# Router.net
KiCad netlist of a schematic drawn in EAGLE
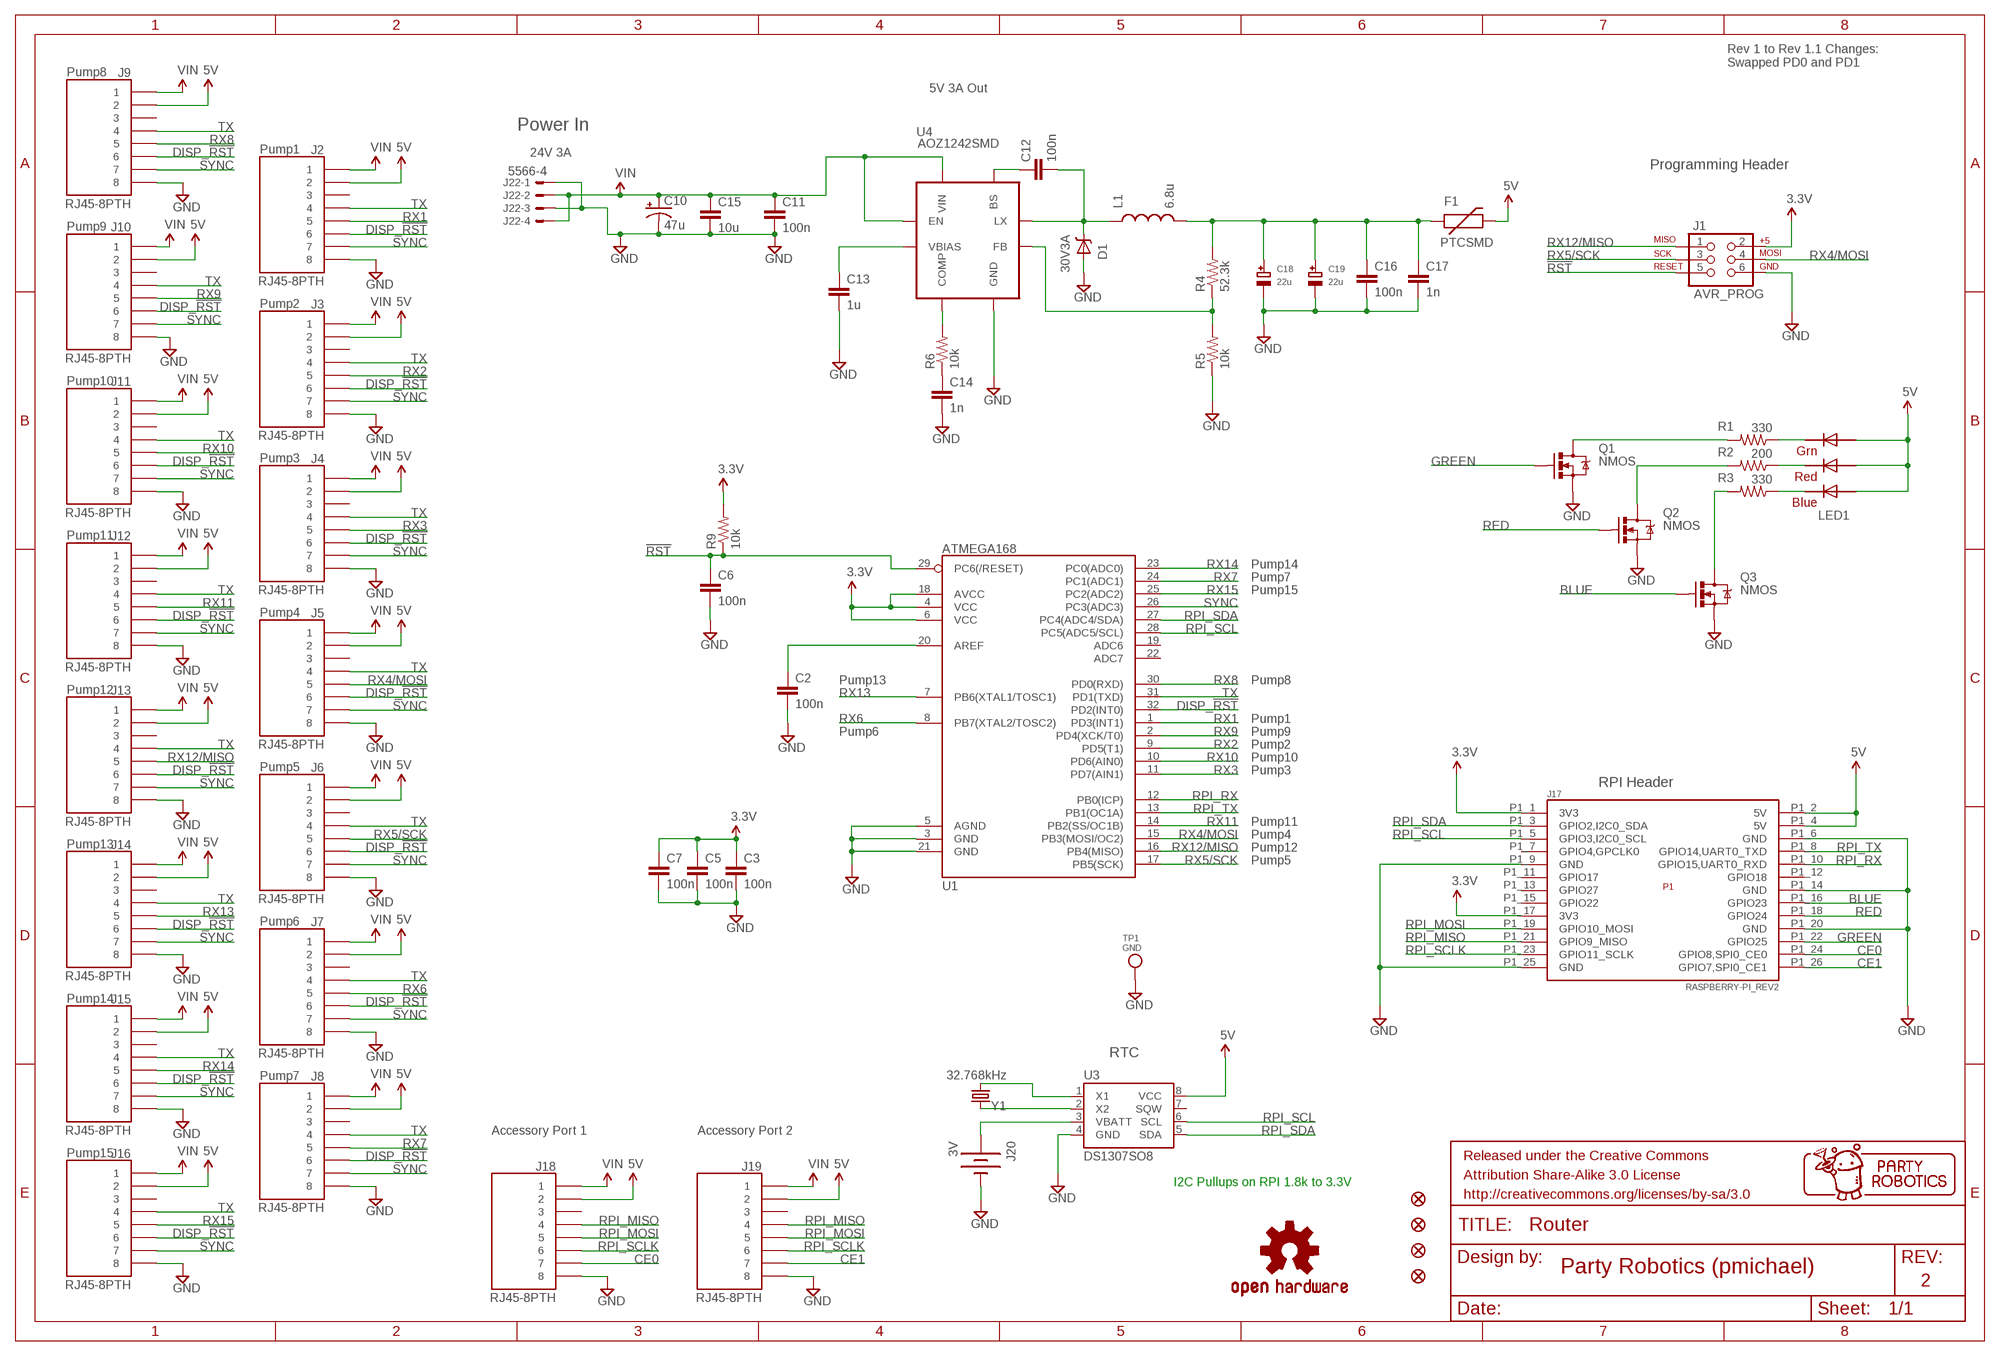
[diagram p0: schematic, sheet 1]

(export (version "E")
  (design (tool "Eeschema 10.0.6"))
  (components
    (comp (ref "C2")
      (value "100n")
      (footprint "eagle-import:0603-CAP")
      (libsource (lib "eagle-import") (part "CAP0603-CAP"))
    )
    (comp (ref "C3")
      (value "100n")
      (footprint "eagle-import:0603-CAP")
      (libsource (lib "eagle-import") (part "CAP0603-CAP"))
    )
    (comp (ref "C5")
      (value "100n")
      (footprint "eagle-import:0603-CAP")
      (libsource (lib "eagle-import") (part "CAP0603-CAP"))
    )
    (comp (ref "C6")
      (value "100n")
      (footprint "eagle-import:0603-CAP")
      (libsource (lib "eagle-import") (part "CAP0603-CAP"))
    )
    (comp (ref "C7")
      (value "100n")
      (footprint "eagle-import:0603-CAP")
      (libsource (lib "eagle-import") (part "CAP0603-CAP"))
    )
    (comp (ref "C10")
      (value "47u")
      (footprint "eagle-import:PANASONIC_D")
      (libsource (lib "eagle-import") (part "CAP_POLD"))
    )
    (comp (ref "C11")
      (value "100n")
      (footprint "eagle-import:0603-CAP")
      (libsource (lib "eagle-import") (part "CAP0603-CAP"))
    )
    (comp (ref "C12")
      (value "100n")
      (footprint "eagle-import:0603-CAP")
      (libsource (lib "eagle-import") (part "CAP0603-CAP"))
    )
    (comp (ref "C13")
      (value "1u")
      (footprint "eagle-import:0603-CAP")
      (libsource (lib "eagle-import") (part "CAP0603-CAP"))
    )
    (comp (ref "C14")
      (value "1n")
      (footprint "eagle-import:0603-CAP")
      (libsource (lib "eagle-import") (part "CAP0603-CAP"))
    )
    (comp (ref "C15")
      (value "10u")
      (footprint "eagle-import:1206")
      (libsource (lib "eagle-import") (part "SparkFun-Capacitors_CAP1206"))
    )
    (comp (ref "C16")
      (value "100n")
      (footprint "eagle-import:0603-CAP")
      (libsource (lib "eagle-import") (part "CAP0603-CAP"))
    )
    (comp (ref "C17")
      (value "1n")
      (footprint "eagle-import:0603-CAP")
      (libsource (lib "eagle-import") (part "CAP0603-CAP"))
    )
    (comp (ref "C18")
      (value "22u")
      (footprint "eagle-import:EIA6032-28_C-R")
      (libsource (lib "eagle-import") (part "CAP_TANTALUMC/6032_REFLOW"))
    )
    (comp (ref "C19")
      (value "22u")
      (footprint "eagle-import:EIA6032-28_C-R")
      (libsource (lib "eagle-import") (part "CAP_TANTALUMC/6032_REFLOW"))
    )
    (comp (ref "D1")
      (value "30V3A")
      (footprint "eagle-import:SMA-DIODE")
      (libsource (lib "eagle-import") (part "B330A"))
    )
    (comp (ref "F1")
      (value "PTCSMD")
      (footprint "eagle-import:PTC-1206")
      (libsource (lib "eagle-import") (part "PTCSMD"))
    )
    (comp (ref "FRAME3")
      (value "FRAME-LETTER")
      (footprint "eagle-import:CREATIVE_COMMONS")
      (libsource (lib "eagle-import") (part "FRAME-LETTER"))
    )
    (comp (ref "J1")
      (value "AVR_PROG")
      (footprint "eagle-import:2X3_LOCK")
      (libsource (lib "eagle-import") (part "AVR_SPI_PRG_62X3_LOCK"))
    )
    (comp (ref "J2")
      (value "RJ45-8PTH")
      (footprint "eagle-import:RJ45-8")
      (fields
        (field (name "MFG") "EDAC Inc")
        (field (name "DIST") "DigiKey")
        (field (name "DIST_PN") "151-1099-ND")
        (field (name "MFG_1") "EDAC Inc")
        (field (name "MFG_PN") "A00-108-220-450")
      )
      (libsource (lib "eagle-import") (part "RJ45-8PTH"))
    )
    (comp (ref "J3")
      (value "RJ45-8PTH")
      (footprint "eagle-import:RJ45-8")
      (fields
        (field (name "MFG") "EDAC Inc")
        (field (name "DIST") "DigiKey")
        (field (name "DIST_PN") "151-1099-ND")
        (field (name "MFG_1") "EDAC Inc")
        (field (name "MFG_PN") "A00-108-220-450")
      )
      (libsource (lib "eagle-import") (part "RJ45-8PTH"))
    )
    (comp (ref "J4")
      (value "RJ45-8PTH")
      (footprint "eagle-import:RJ45-8")
      (fields
        (field (name "MFG") "EDAC Inc")
        (field (name "DIST") "DigiKey")
        (field (name "DIST_PN") "151-1099-ND")
        (field (name "MFG_1") "EDAC Inc")
        (field (name "MFG_PN") "A00-108-220-450")
      )
      (libsource (lib "eagle-import") (part "RJ45-8PTH"))
    )
    (comp (ref "J5")
      (value "RJ45-8PTH")
      (footprint "eagle-import:RJ45-8")
      (fields
        (field (name "MFG") "EDAC Inc")
        (field (name "DIST") "DigiKey")
        (field (name "DIST_PN") "151-1099-ND")
        (field (name "MFG_1") "EDAC Inc")
        (field (name "MFG_PN") "A00-108-220-450")
      )
      (libsource (lib "eagle-import") (part "RJ45-8PTH"))
    )
    (comp (ref "J6")
      (value "RJ45-8PTH")
      (footprint "eagle-import:RJ45-8")
      (fields
        (field (name "MFG") "EDAC Inc")
        (field (name "DIST") "DigiKey")
        (field (name "DIST_PN") "151-1099-ND")
        (field (name "MFG_1") "EDAC Inc")
        (field (name "MFG_PN") "A00-108-220-450")
      )
      (libsource (lib "eagle-import") (part "RJ45-8PTH"))
    )
    (comp (ref "J7")
      (value "RJ45-8PTH")
      (footprint "eagle-import:RJ45-8")
      (fields
        (field (name "MFG") "EDAC Inc")
        (field (name "DIST") "DigiKey")
        (field (name "DIST_PN") "151-1099-ND")
        (field (name "MFG_1") "EDAC Inc")
        (field (name "MFG_PN") "A00-108-220-450")
      )
      (libsource (lib "eagle-import") (part "RJ45-8PTH"))
    )
    (comp (ref "J8")
      (value "RJ45-8PTH")
      (footprint "eagle-import:RJ45-8")
      (fields
        (field (name "MFG") "EDAC Inc")
        (field (name "DIST") "DigiKey")
        (field (name "DIST_PN") "151-1099-ND")
        (field (name "MFG_1") "EDAC Inc")
        (field (name "MFG_PN") "A00-108-220-450")
      )
      (libsource (lib "eagle-import") (part "RJ45-8PTH"))
    )
    (comp (ref "J9")
      (value "RJ45-8PTH")
      (footprint "eagle-import:RJ45-8")
      (fields (field (name "MFG") "EDAC Inc"))
      (libsource (lib "eagle-import") (part "RJ45-8PTH"))
    )
    (comp (ref "J10")
      (value "RJ45-8PTH")
      (footprint "eagle-import:RJ45-8")
      (fields
        (field (name "MFG") "EDAC Inc")
        (field (name "DIST") "DigiKey")
        (field (name "DIST_PN") "151-1099-ND")
        (field (name "MFG_1") "EDAC Inc")
        (field (name "MFG_PN") "A00-108-220-450")
      )
      (libsource (lib "eagle-import") (part "RJ45-8PTH"))
    )
    (comp (ref "J11")
      (value "RJ45-8PTH")
      (footprint "eagle-import:RJ45-8")
      (fields
        (field (name "MFG") "EDAC Inc")
        (field (name "DIST") "DigiKey")
        (field (name "DIST_PN") "151-1099-ND")
        (field (name "MFG_1") "EDAC Inc")
        (field (name "MFG_PN") "A00-108-220-450")
      )
      (libsource (lib "eagle-import") (part "RJ45-8PTH"))
    )
    (comp (ref "J12")
      (value "RJ45-8PTH")
      (footprint "eagle-import:RJ45-8")
      (fields
        (field (name "MFG") "EDAC Inc")
        (field (name "DIST") "DigiKey")
        (field (name "DIST_PN") "151-1099-ND")
        (field (name "MFG_1") "EDAC Inc")
        (field (name "MFG_PN") "A00-108-220-450")
      )
      (libsource (lib "eagle-import") (part "RJ45-8PTH"))
    )
    (comp (ref "J13")
      (value "RJ45-8PTH")
      (footprint "eagle-import:RJ45-8")
      (fields
        (field (name "MFG") "EDAC Inc")
        (field (name "DIST") "DigiKey")
        (field (name "DIST_PN") "151-1099-ND")
        (field (name "MFG_1") "EDAC Inc")
        (field (name "MFG_PN") "A00-108-220-450")
      )
      (libsource (lib "eagle-import") (part "RJ45-8PTH"))
    )
    (comp (ref "J14")
      (value "RJ45-8PTH")
      (footprint "eagle-import:RJ45-8")
      (fields
        (field (name "MFG") "EDAC Inc")
        (field (name "DIST") "DigiKey")
        (field (name "DIST_PN") "151-1099-ND")
        (field (name "MFG_1") "EDAC Inc")
        (field (name "MFG_PN") "A00-108-220-450")
      )
      (libsource (lib "eagle-import") (part "RJ45-8PTH"))
    )
    (comp (ref "J15")
      (value "RJ45-8PTH")
      (footprint "eagle-import:RJ45-8")
      (fields
        (field (name "MFG") "EDAC Inc")
        (field (name "DIST") "DigiKey")
        (field (name "DIST_PN") "151-1099-ND")
        (field (name "MFG_1") "EDAC Inc")
        (field (name "MFG_PN") "A00-108-220-450")
      )
      (libsource (lib "eagle-import") (part "RJ45-8PTH"))
    )
    (comp (ref "J16")
      (value "RJ45-8PTH")
      (footprint "eagle-import:RJ45-8")
      (fields
        (field (name "MFG") "EDAC Inc")
        (field (name "DIST") "DigiKey")
        (field (name "DIST_PN") "151-1099-ND")
        (field (name "MFG_1") "EDAC Inc")
        (field (name "MFG_PN") "A00-108-220-450")
      )
      (libsource (lib "eagle-import") (part "RJ45-8PTH"))
    )
    (comp (ref "J17")
      (value "RASPBERRY-PI_REV2")
      (footprint "eagle-import:RASPBERRY-PI_REV2")
      (libsource (lib "eagle-import") (part "RASPBERRY-PI_REV2"))
    )
    (comp (ref "J18")
      (value "RJ45-8PTH")
      (footprint "eagle-import:RJ45-8")
      (fields
        (field (name "MFG") "EDAC Inc")
        (field (name "DIST") "DigiKey")
        (field (name "DIST_PN") "151-1099-ND")
        (field (name "MFG_1") "EDAC Inc")
        (field (name "MFG_PN") "A00-108-220-450")
      )
      (libsource (lib "eagle-import") (part "RJ45-8PTH"))
    )
    (comp (ref "J19")
      (value "RJ45-8PTH")
      (footprint "eagle-import:RJ45-8")
      (fields
        (field (name "MFG") "EDAC Inc")
        (field (name "DIST") "DigiKey")
        (field (name "DIST_PN") "151-1099-ND")
        (field (name "MFG_1") "EDAC Inc")
        (field (name "MFG_PN") "A00-108-220-450")
      )
      (libsource (lib "eagle-import") (part "RJ45-8PTH"))
    )
    (comp (ref "J20")
      (value "3V")
      (footprint "eagle-import:BATTCON_12MM_PTH")
      (libsource (lib "eagle-import") (part "BATTERY12PTH"))
    )
    (comp (ref "J22")
      (value "5566-4")
      (footprint "eagle-import:5566-4")
      (libsource (lib "eagle-import") (part "5566-4"))
    )
    (comp (ref "JP1")
      (value "FIDUCIAL1.5X3")
      (footprint "eagle-import:FIDUCIAL-1.5X3")
      (libsource (lib "eagle-import") (part "FIDUCIAL1.5X3"))
    )
    (comp (ref "JP2")
      (value "FIDUCIAL1.5X3")
      (footprint "eagle-import:FIDUCIAL-1.5X3")
      (libsource (lib "eagle-import") (part "FIDUCIAL1.5X3"))
    )
    (comp (ref "JP3")
      (value "FIDUCIAL1.5X3")
      (footprint "eagle-import:FIDUCIAL-1.5X3")
      (libsource (lib "eagle-import") (part "FIDUCIAL1.5X3"))
    )
    (comp (ref "JP4")
      (value "FIDUCIAL1.5X3")
      (footprint "eagle-import:FIDUCIAL-1.5X3")
      (libsource (lib "eagle-import") (part "FIDUCIAL1.5X3"))
    )
    (comp (ref "L1")
      (value "6.8u")
      (footprint "eagle-import:IND_8X8X4")
      (libsource (lib "eagle-import") (part "INDUCTORCR54"))
    )
    (comp (ref "LED1")
      (value "RGBLED5050")
      (footprint "eagle-import:RGBLED5050")
      (libsource (lib "eagle-import") (part "RGBLED5050"))
    )
    (comp (ref "Q1")
      (value "NMOS")
      (footprint "eagle-import:SOT23-3")
      (libsource (lib "eagle-import") (part "MOSFET-NCHANNELSMD"))
    )
    (comp (ref "Q2")
      (value "NMOS")
      (footprint "eagle-import:SOT23-3")
      (libsource (lib "eagle-import") (part "MOSFET-NCHANNELSMD"))
    )
    (comp (ref "Q3")
      (value "NMOS")
      (footprint "eagle-import:SOT23-3")
      (libsource (lib "eagle-import") (part "MOSFET-NCHANNELSMD"))
    )
    (comp (ref "R1")
      (value "330")
      (footprint "eagle-import:0603-RES")
      (libsource (lib "eagle-import") (part "RESISTOR0603-RES"))
    )
    (comp (ref "R2")
      (value "200")
      (footprint "eagle-import:0603-RES")
      (libsource (lib "eagle-import") (part "RESISTOR0603-RES"))
    )
    (comp (ref "R3")
      (value "330")
      (footprint "eagle-import:0603-RES")
      (libsource (lib "eagle-import") (part "RESISTOR0603-RES"))
    )
    (comp (ref "R4")
      (value "52.3k")
      (footprint "eagle-import:0603-RES")
      (libsource (lib "eagle-import") (part "RESISTOR0603-RES"))
    )
    (comp (ref "R5")
      (value "10k")
      (footprint "eagle-import:0603-RES")
      (libsource (lib "eagle-import") (part "RESISTOR0603-RES"))
    )
    (comp (ref "R6")
      (value "10k")
      (footprint "eagle-import:0603-RES")
      (libsource (lib "eagle-import") (part "RESISTOR0603-RES"))
    )
    (comp (ref "R9")
      (value "10k")
      (footprint "eagle-import:0603-RES")
      (libsource (lib "eagle-import") (part "RESISTOR0603-RES"))
    )
    (comp (ref "TP1")
      (value "GND")
      (footprint "eagle-import:TESTPOINT_SMT")
      (libsource (lib "eagle-import") (part "TESTPOINT"))
    )
    (comp (ref "U$46")
      (value "OSHW-LOGOM")
      (footprint "eagle-import:OSHW-LOGO-M")
      (libsource (lib "eagle-import") (part "OSHW-LOGOM"))
    )
    (comp (ref "U1")
      (value "ATMEGA168")
      (footprint "eagle-import:TQFP32-08")
      (libsource (lib "eagle-import") (part "ATMEGA168"))
    )
    (comp (ref "U3")
      (value "DS1307SO8")
      (footprint "eagle-import:SO08")
      (libsource (lib "eagle-import") (part "DS1307SO8"))
    )
    (comp (ref "U4")
      (value "AOZ1242SMD")
      (footprint "eagle-import:SO08")
      (libsource (lib "eagle-import") (part "AOZ1242SMD"))
    )
    (comp (ref "Y1")
      (value "32.768kHz")
      (footprint "eagle-import:TC26HEZ")
      (libsource (lib "eagle-import") (part "CRYSTALTC26H_EZ"))
    )
  )
  (nets
    (net (code "1") (name "/BLUE") (class "Default")
      (node (ref "J17") (pin "P1_16") (pinfunction "GPIO23_P1_16") (pintype "bidirectional"))
      (node (ref "Q3") (pin "1") (pinfunction "G_1") (pintype "passive"))
    )
    (net (code "2") (name "/CE0") (class "Default")
      (node (ref "J17") (pin "P1_24") (pinfunction "GPIO8,SPI0_CE0_P1_24") (pintype "bidirectional"))
      (node (ref "J18") (pin "7") (pinfunction "7_7") (pintype "bidirectional"))
    )
    (net (code "3") (name "/CE1") (class "Default")
      (node (ref "J17") (pin "P1_26") (pinfunction "GPIO7,SPI0_CE1_P1_26") (pintype "bidirectional"))
      (node (ref "J19") (pin "7") (pinfunction "7_7") (pintype "bidirectional"))
    )
    (net (code "4") (name "/DISP_~{RST}") (class "Default")
      (node (ref "J10") (pin "6") (pinfunction "6_6") (pintype "bidirectional"))
      (node (ref "J11") (pin "6") (pinfunction "6_6") (pintype "bidirectional"))
      (node (ref "J12") (pin "6") (pinfunction "6_6") (pintype "bidirectional"))
      (node (ref "J13") (pin "6") (pinfunction "6_6") (pintype "bidirectional"))
      (node (ref "J14") (pin "6") (pinfunction "6_6") (pintype "bidirectional"))
      (node (ref "J15") (pin "6") (pinfunction "6_6") (pintype "bidirectional"))
      (node (ref "J16") (pin "6") (pinfunction "6_6") (pintype "bidirectional"))
      (node (ref "J2") (pin "6") (pinfunction "6_6") (pintype "bidirectional"))
      (node (ref "J3") (pin "6") (pinfunction "6_6") (pintype "bidirectional"))
      (node (ref "J4") (pin "6") (pinfunction "6_6") (pintype "bidirectional"))
      (node (ref "J5") (pin "6") (pinfunction "6_6") (pintype "bidirectional"))
      (node (ref "J6") (pin "6") (pinfunction "6_6") (pintype "bidirectional"))
      (node (ref "J7") (pin "6") (pinfunction "6_6") (pintype "bidirectional"))
      (node (ref "J8") (pin "6") (pinfunction "6_6") (pintype "bidirectional"))
      (node (ref "J9") (pin "6") (pinfunction "6_6") (pintype "bidirectional"))
      (node (ref "U1") (pin "32") (pinfunction "PD2(INT0)_32") (pintype "bidirectional"))
    )
    (net (code "5") (name "/GREEN") (class "Default")
      (node (ref "J17") (pin "P1_22") (pinfunction "GPIO25_P1_22") (pintype "bidirectional"))
      (node (ref "Q1") (pin "1") (pinfunction "G_1") (pintype "passive"))
    )
    (net (code "6") (name "/RED") (class "Default")
      (node (ref "J17") (pin "P1_18") (pinfunction "GPIO24_P1_18") (pintype "bidirectional"))
      (node (ref "Q2") (pin "1") (pinfunction "G_1") (pintype "passive"))
    )
    (net (code "7") (name "/RPI_MISO") (class "Default")
      (node (ref "J17") (pin "P1_21") (pinfunction "GPIO9_MISO_P1_21") (pintype "bidirectional"))
      (node (ref "J18") (pin "4") (pinfunction "4_4") (pintype "bidirectional"))
      (node (ref "J19") (pin "4") (pinfunction "4_4") (pintype "bidirectional"))
    )
    (net (code "8") (name "/RPI_MOSI") (class "Default")
      (node (ref "J17") (pin "P1_19") (pinfunction "GPIO10_MOSI_P1_19") (pintype "bidirectional"))
      (node (ref "J18") (pin "5") (pinfunction "5_5") (pintype "bidirectional"))
      (node (ref "J19") (pin "5") (pinfunction "5_5") (pintype "bidirectional"))
    )
    (net (code "9") (name "/RPI_RX") (class "Default")
      (node (ref "J17") (pin "P1_10") (pinfunction "GPIO15,UART0_RXD_P1_10") (pintype "bidirectional"))
      (node (ref "U1") (pin "12") (pinfunction "PB0(ICP)_12") (pintype "bidirectional"))
    )
    (net (code "10") (name "/RPI_SCL") (class "Default")
      (node (ref "J17") (pin "P1_5") (pinfunction "GPIO3,I2C0_SCL_P1_5") (pintype "bidirectional"))
      (node (ref "U1") (pin "28") (pinfunction "PC5(ADC5/SCL)_28") (pintype "bidirectional"))
      (node (ref "U3") (pin "6") (pinfunction "SCL_6") (pintype "bidirectional"))
    )
    (net (code "11") (name "/RPI_SCLK") (class "Default")
      (node (ref "J17") (pin "P1_23") (pinfunction "GPIO11_SCLK_P1_23") (pintype "bidirectional"))
      (node (ref "J18") (pin "6") (pinfunction "6_6") (pintype "bidirectional"))
      (node (ref "J19") (pin "6") (pinfunction "6_6") (pintype "bidirectional"))
    )
    (net (code "12") (name "/RPI_SDA") (class "Default")
      (node (ref "J17") (pin "P1_3") (pinfunction "GPIO2,I2C0_SDA_P1_3") (pintype "bidirectional"))
      (node (ref "U1") (pin "27") (pinfunction "PC4(ADC4/SDA)_27") (pintype "bidirectional"))
      (node (ref "U3") (pin "5") (pinfunction "SDA_5") (pintype "bidirectional"))
    )
    (net (code "13") (name "/RPI_TX") (class "Default")
      (node (ref "J17") (pin "P1_8") (pinfunction "GPIO14,UART0_TXD_P1_8") (pintype "bidirectional"))
      (node (ref "U1") (pin "13") (pinfunction "PB1(OC1A)_13") (pintype "bidirectional"))
    )
    (net (code "14") (name "/RX1") (class "Default")
      (node (ref "J2") (pin "5") (pinfunction "5_5") (pintype "bidirectional"))
      (node (ref "U1") (pin "1") (pinfunction "PD3(INT1)_1") (pintype "bidirectional"))
    )
    (net (code "15") (name "/RX2") (class "Default")
      (node (ref "J3") (pin "5") (pinfunction "5_5") (pintype "bidirectional"))
      (node (ref "U1") (pin "9") (pinfunction "PD5(T1)_9") (pintype "bidirectional"))
    )
    (net (code "16") (name "/RX3") (class "Default")
      (node (ref "J4") (pin "5") (pinfunction "5_5") (pintype "bidirectional"))
      (node (ref "U1") (pin "11") (pinfunction "PD7(AIN1)_11") (pintype "bidirectional"))
    )
    (net (code "17") (name "/RX4{slash}MOSI") (class "Default")
      (node (ref "J1") (pin "4") (pinfunction "4_4") (pintype "passive"))
      (node (ref "J5") (pin "5") (pinfunction "5_5") (pintype "bidirectional"))
      (node (ref "U1") (pin "15") (pinfunction "PB3(MOSI/OC2)_15") (pintype "bidirectional"))
    )
    (net (code "18") (name "/RX5{slash}SCK") (class "Default")
      (node (ref "J1") (pin "3") (pinfunction "3_3") (pintype "passive"))
      (node (ref "J6") (pin "5") (pinfunction "5_5") (pintype "bidirectional"))
      (node (ref "U1") (pin "17") (pinfunction "PB5(SCK)_17") (pintype "bidirectional"))
    )
    (net (code "19") (name "/RX6") (class "Default")
      (node (ref "J7") (pin "5") (pinfunction "5_5") (pintype "bidirectional"))
      (node (ref "U1") (pin "8") (pinfunction "PB7(XTAL2/TOSC2)_8") (pintype "bidirectional"))
    )
    (net (code "20") (name "/RX7") (class "Default")
      (node (ref "J8") (pin "5") (pinfunction "5_5") (pintype "bidirectional"))
      (node (ref "U1") (pin "24") (pinfunction "PC1(ADC1)_24") (pintype "bidirectional"))
    )
    (net (code "21") (name "/RX8") (class "Default")
      (node (ref "J9") (pin "5") (pinfunction "5_5") (pintype "bidirectional"))
      (node (ref "U1") (pin "30") (pinfunction "PD0(RXD)_30") (pintype "bidirectional"))
    )
    (net (code "22") (name "/RX9") (class "Default")
      (node (ref "J10") (pin "5") (pinfunction "5_5") (pintype "bidirectional"))
      (node (ref "U1") (pin "2") (pinfunction "PD4(XCK/T0)_2") (pintype "bidirectional"))
    )
    (net (code "23") (name "/RX10") (class "Default")
      (node (ref "J11") (pin "5") (pinfunction "5_5") (pintype "bidirectional"))
      (node (ref "U1") (pin "10") (pinfunction "PD6(AIN0)_10") (pintype "bidirectional"))
    )
    (net (code "24") (name "/RX11") (class "Default")
      (node (ref "J12") (pin "5") (pinfunction "5_5") (pintype "bidirectional"))
      (node (ref "U1") (pin "14") (pinfunction "PB2(SS/OC1B)_14") (pintype "bidirectional"))
    )
    (net (code "25") (name "/RX12{slash}MISO") (class "Default")
      (node (ref "J1") (pin "1") (pinfunction "1_1") (pintype "passive"))
      (node (ref "J13") (pin "5") (pinfunction "5_5") (pintype "bidirectional"))
      (node (ref "U1") (pin "16") (pinfunction "PB4(MISO)_16") (pintype "bidirectional"))
    )
    (net (code "26") (name "/RX13") (class "Default")
      (node (ref "J14") (pin "5") (pinfunction "5_5") (pintype "bidirectional"))
      (node (ref "U1") (pin "7") (pinfunction "PB6(XTAL1/TOSC1)_7") (pintype "bidirectional"))
    )
    (net (code "27") (name "/RX14") (class "Default")
      (node (ref "J15") (pin "5") (pinfunction "5_5") (pintype "bidirectional"))
      (node (ref "U1") (pin "23") (pinfunction "PC0(ADC0)_23") (pintype "bidirectional"))
    )
    (net (code "28") (name "/RX15") (class "Default")
      (node (ref "J16") (pin "5") (pinfunction "5_5") (pintype "bidirectional"))
      (node (ref "U1") (pin "25") (pinfunction "PC2(ADC2)_25") (pintype "bidirectional"))
    )
    (net (code "29") (name "/SYNC") (class "Default")
      (node (ref "J10") (pin "7") (pinfunction "7_7") (pintype "bidirectional"))
      (node (ref "J11") (pin "7") (pinfunction "7_7") (pintype "bidirectional"))
      (node (ref "J12") (pin "7") (pinfunction "7_7") (pintype "bidirectional"))
      (node (ref "J13") (pin "7") (pinfunction "7_7") (pintype "bidirectional"))
      (node (ref "J14") (pin "7") (pinfunction "7_7") (pintype "bidirectional"))
      (node (ref "J15") (pin "7") (pinfunction "7_7") (pintype "bidirectional"))
      (node (ref "J16") (pin "7") (pinfunction "7_7") (pintype "bidirectional"))
      (node (ref "J2") (pin "7") (pinfunction "7_7") (pintype "bidirectional"))
      (node (ref "J3") (pin "7") (pinfunction "7_7") (pintype "bidirectional"))
      (node (ref "J4") (pin "7") (pinfunction "7_7") (pintype "bidirectional"))
      (node (ref "J5") (pin "7") (pinfunction "7_7") (pintype "bidirectional"))
      (node (ref "J6") (pin "7") (pinfunction "7_7") (pintype "bidirectional"))
      (node (ref "J7") (pin "7") (pinfunction "7_7") (pintype "bidirectional"))
      (node (ref "J8") (pin "7") (pinfunction "7_7") (pintype "bidirectional"))
      (node (ref "J9") (pin "7") (pinfunction "7_7") (pintype "bidirectional"))
      (node (ref "U1") (pin "26") (pinfunction "PC3(ADC3)_26") (pintype "bidirectional"))
    )
    (net (code "30") (name "/TX") (class "Default")
      (node (ref "J10") (pin "4") (pinfunction "4_4") (pintype "bidirectional"))
      (node (ref "J11") (pin "4") (pinfunction "4_4") (pintype "bidirectional"))
      (node (ref "J12") (pin "4") (pinfunction "4_4") (pintype "bidirectional"))
      (node (ref "J13") (pin "4") (pinfunction "4_4") (pintype "bidirectional"))
      (node (ref "J14") (pin "4") (pinfunction "4_4") (pintype "bidirectional"))
      (node (ref "J15") (pin "4") (pinfunction "4_4") (pintype "bidirectional"))
      (node (ref "J16") (pin "4") (pinfunction "4_4") (pintype "bidirectional"))
      (node (ref "J2") (pin "4") (pinfunction "4_4") (pintype "bidirectional"))
      (node (ref "J3") (pin "4") (pinfunction "4_4") (pintype "bidirectional"))
      (node (ref "J4") (pin "4") (pinfunction "4_4") (pintype "bidirectional"))
      (node (ref "J5") (pin "4") (pinfunction "4_4") (pintype "bidirectional"))
      (node (ref "J6") (pin "4") (pinfunction "4_4") (pintype "bidirectional"))
      (node (ref "J7") (pin "4") (pinfunction "4_4") (pintype "bidirectional"))
      (node (ref "J8") (pin "4") (pinfunction "4_4") (pintype "bidirectional"))
      (node (ref "J9") (pin "4") (pinfunction "4_4") (pintype "bidirectional"))
      (node (ref "U1") (pin "31") (pinfunction "PD1(TXD)_31") (pintype "bidirectional"))
    )
    (net (code "31") (name "/~{RST}") (class "Default")
      (node (ref "C6") (pin "1") (pinfunction "1_1") (pintype "passive"))
      (node (ref "J1") (pin "5") (pinfunction "5_5") (pintype "passive"))
      (node (ref "R9") (pin "1") (pinfunction "1_1") (pintype "passive"))
      (node (ref "U1") (pin "29") (pinfunction "PC6(/RESET)_29") (pintype "bidirectional"))
    )
    (net (code "32") (name "3.3V") (class "Default")
      (node (ref "C3") (pin "1") (pinfunction "1_1") (pintype "passive"))
      (node (ref "C5") (pin "1") (pinfunction "1_1") (pintype "passive"))
      (node (ref "C7") (pin "1") (pinfunction "1_1") (pintype "passive"))
      (node (ref "J1") (pin "2") (pinfunction "2_2") (pintype "passive"))
      (node (ref "J17") (pin "P1_1") (pinfunction "3V3_P1_1") (pintype "bidirectional"))
      (node (ref "J17") (pin "P1_17") (pinfunction "3V3_P1_17") (pintype "bidirectional"))
      (node (ref "R9") (pin "2") (pinfunction "2_2") (pintype "passive"))
      (node (ref "U1") (pin "18") (pinfunction "AVCC_18") (pintype "bidirectional"))
      (node (ref "U1") (pin "4") (pinfunction "VCC_4") (pintype "bidirectional"))
      (node (ref "U1") (pin "6") (pinfunction "VCC_6") (pintype "bidirectional"))
    )
    (net (code "33") (name "5V") (class "Default")
      (node (ref "F1") (pin "2") (pinfunction "2_2") (pintype "bidirectional"))
      (node (ref "J10") (pin "2") (pinfunction "2_2") (pintype "bidirectional"))
      (node (ref "J11") (pin "2") (pinfunction "2_2") (pintype "bidirectional"))
      (node (ref "J12") (pin "2") (pinfunction "2_2") (pintype "bidirectional"))
      (node (ref "J13") (pin "2") (pinfunction "2_2") (pintype "bidirectional"))
      (node (ref "J14") (pin "2") (pinfunction "2_2") (pintype "bidirectional"))
      (node (ref "J15") (pin "2") (pinfunction "2_2") (pintype "bidirectional"))
      (node (ref "J16") (pin "2") (pinfunction "2_2") (pintype "bidirectional"))
      (node (ref "J17") (pin "P1_2") (pinfunction "5V_P1_2") (pintype "bidirectional"))
      (node (ref "J17") (pin "P1_4") (pinfunction "5V_P1_4") (pintype "bidirectional"))
      (node (ref "J18") (pin "2") (pinfunction "2_2") (pintype "bidirectional"))
      (node (ref "J19") (pin "2") (pinfunction "2_2") (pintype "bidirectional"))
      (node (ref "J2") (pin "2") (pinfunction "2_2") (pintype "bidirectional"))
      (node (ref "J3") (pin "2") (pinfunction "2_2") (pintype "bidirectional"))
      (node (ref "J4") (pin "2") (pinfunction "2_2") (pintype "bidirectional"))
      (node (ref "J5") (pin "2") (pinfunction "2_2") (pintype "bidirectional"))
      (node (ref "J6") (pin "2") (pinfunction "2_2") (pintype "bidirectional"))
      (node (ref "J7") (pin "2") (pinfunction "2_2") (pintype "bidirectional"))
      (node (ref "J8") (pin "2") (pinfunction "2_2") (pintype "bidirectional"))
      (node (ref "J9") (pin "2") (pinfunction "2_2") (pintype "bidirectional"))
      (node (ref "LED1") (pin "1") (pinfunction "BLUE_A_1") (pintype "bidirectional"))
      (node (ref "LED1") (pin "2") (pinfunction "RED_A_2") (pintype "bidirectional"))
      (node (ref "LED1") (pin "3") (pinfunction "GREEN_A_3") (pintype "bidirectional"))
      (node (ref "U3") (pin "8") (pinfunction "VCC_8") (pintype "bidirectional"))
    )
    (net (code "34") (name "GND") (class "Default")
      (node (ref "C10") (pin "-") (pinfunction "-_-") (pintype "passive"))
      (node (ref "C11") (pin "2") (pinfunction "2_2") (pintype "passive"))
      (node (ref "C13") (pin "2") (pinfunction "2_2") (pintype "passive"))
      (node (ref "C14") (pin "2") (pinfunction "2_2") (pintype "passive"))
      (node (ref "C15") (pin "2") (pinfunction "2_2") (pintype "passive"))
      (node (ref "C16") (pin "2") (pinfunction "2_2") (pintype "passive"))
      (node (ref "C17") (pin "2") (pinfunction "2_2") (pintype "passive"))
      (node (ref "C18") (pin "-") (pinfunction "-_-") (pintype "passive"))
      (node (ref "C19") (pin "-") (pinfunction "-_-") (pintype "passive"))
      (node (ref "C2") (pin "2") (pinfunction "2_2") (pintype "passive"))
      (node (ref "C3") (pin "2") (pinfunction "2_2") (pintype "passive"))
      (node (ref "C5") (pin "2") (pinfunction "2_2") (pintype "passive"))
      (node (ref "C6") (pin "2") (pinfunction "2_2") (pintype "passive"))
      (node (ref "C7") (pin "2") (pinfunction "2_2") (pintype "passive"))
      (node (ref "D1") (pin "A") (pinfunction "A_A") (pintype "passive"))
      (node (ref "J1") (pin "6") (pinfunction "6_6") (pintype "passive"))
      (node (ref "J10") (pin "8") (pinfunction "8_8") (pintype "bidirectional"))
      (node (ref "J11") (pin "8") (pinfunction "8_8") (pintype "bidirectional"))
      (node (ref "J12") (pin "8") (pinfunction "8_8") (pintype "bidirectional"))
      (node (ref "J13") (pin "8") (pinfunction "8_8") (pintype "bidirectional"))
      (node (ref "J14") (pin "8") (pinfunction "8_8") (pintype "bidirectional"))
      (node (ref "J15") (pin "8") (pinfunction "8_8") (pintype "bidirectional"))
      (node (ref "J16") (pin "8") (pinfunction "8_8") (pintype "bidirectional"))
      (node (ref "J17") (pin "P1_14") (pinfunction "GND_P1_14") (pintype "bidirectional"))
      (node (ref "J17") (pin "P1_20") (pinfunction "GND_P1_20") (pintype "bidirectional"))
      (node (ref "J17") (pin "P1_25") (pinfunction "GND_P1_25") (pintype "bidirectional"))
      (node (ref "J17") (pin "P1_6") (pinfunction "GND_P1_6") (pintype "bidirectional"))
      (node (ref "J17") (pin "P1_9") (pinfunction "GND_P1_9") (pintype "bidirectional"))
      (node (ref "J18") (pin "8") (pinfunction "8_8") (pintype "bidirectional"))
      (node (ref "J19") (pin "8") (pinfunction "8_8") (pintype "bidirectional"))
      (node (ref "J2") (pin "8") (pinfunction "8_8") (pintype "bidirectional"))
      (node (ref "J20") (pin "GND") (pinfunction "-_GND") (pintype "power_in"))
      (node (ref "J22") (pin "1") (pinfunction "S_1") (pintype "passive"))
      (node (ref "J22") (pin "3") (pinfunction "S_3") (pintype "passive"))
      (node (ref "J3") (pin "8") (pinfunction "8_8") (pintype "bidirectional"))
      (node (ref "J4") (pin "8") (pinfunction "8_8") (pintype "bidirectional"))
      (node (ref "J5") (pin "8") (pinfunction "8_8") (pintype "bidirectional"))
      (node (ref "J6") (pin "8") (pinfunction "8_8") (pintype "bidirectional"))
      (node (ref "J7") (pin "8") (pinfunction "8_8") (pintype "bidirectional"))
      (node (ref "J8") (pin "8") (pinfunction "8_8") (pintype "bidirectional"))
      (node (ref "J9") (pin "8") (pinfunction "8_8") (pintype "bidirectional"))
      (node (ref "Q1") (pin "2") (pinfunction "S_2") (pintype "passive"))
      (node (ref "Q2") (pin "2") (pinfunction "S_2") (pintype "passive"))
      (node (ref "Q3") (pin "2") (pinfunction "S_2") (pintype "passive"))
      (node (ref "R5") (pin "1") (pinfunction "1_1") (pintype "passive"))
      (node (ref "TP1") (pin "P$1") (pinfunction "P$1_P$1") (pintype "bidirectional"))
      (node (ref "U1") (pin "21") (pinfunction "GND_21") (pintype "bidirectional"))
      (node (ref "U1") (pin "3") (pinfunction "GND_3") (pintype "bidirectional"))
      (node (ref "U1") (pin "5") (pinfunction "AGND_5") (pintype "bidirectional"))
      (node (ref "U3") (pin "4") (pinfunction "GND_4") (pintype "bidirectional"))
      (node (ref "U4") (pin "3") (pinfunction "GND_3") (pintype "bidirectional"))
    )
    (net (code "35") (name "Net-(C14-Pad1)") (class "Default")
      (node (ref "C14") (pin "1") (pinfunction "1_1") (pintype "passive"))
      (node (ref "R6") (pin "1") (pinfunction "1_1") (pintype "passive"))
    )
    (net (code "36") (name "Net-(J20-+)") (class "Default")
      (node (ref "J20") (pin "VCC@1") (pinfunction "+_VCC@1") (pintype "power_in"))
      (node (ref "U3") (pin "3") (pinfunction "VBATT_3") (pintype "bidirectional"))
    )
    (net (code "37") (name "Net-(L1-1)") (class "Default")
      (node (ref "C12") (pin "2") (pinfunction "2_2") (pintype "passive"))
      (node (ref "D1") (pin "C") (pinfunction "C_C") (pintype "passive"))
      (node (ref "L1") (pin "P$1") (pinfunction "1_P$1") (pintype "passive"))
      (node (ref "U4") (pin "1") (pinfunction "LX_1") (pintype "bidirectional"))
    )
    (net (code "38") (name "Net-(L1-2)") (class "Default")
      (node (ref "C16") (pin "1") (pinfunction "1_1") (pintype "passive"))
      (node (ref "C17") (pin "1") (pinfunction "1_1") (pintype "passive"))
      (node (ref "C18") (pin "+") (pinfunction "+_+") (pintype "passive"))
      (node (ref "C19") (pin "+") (pinfunction "+_+") (pintype "passive"))
      (node (ref "F1") (pin "1") (pinfunction "1_1") (pintype "bidirectional"))
      (node (ref "L1") (pin "P$2") (pinfunction "2_P$2") (pintype "passive"))
      (node (ref "R4") (pin "2") (pinfunction "2_2") (pintype "passive"))
    )
    (net (code "39") (name "Net-(LED1-BLUE_C)") (class "Default")
      (node (ref "LED1") (pin "6") (pinfunction "BLUE_C_6") (pintype "bidirectional"))
      (node (ref "R3") (pin "1") (pinfunction "1_1") (pintype "passive"))
    )
    (net (code "40") (name "Net-(LED1-GREEN_C)") (class "Default")
      (node (ref "LED1") (pin "4") (pinfunction "GREEN_C_4") (pintype "bidirectional"))
      (node (ref "R1") (pin "1") (pinfunction "1_1") (pintype "passive"))
    )
    (net (code "41") (name "Net-(LED1-RED_C)") (class "Default")
      (node (ref "LED1") (pin "5") (pinfunction "RED_C_5") (pintype "bidirectional"))
      (node (ref "R2") (pin "1") (pinfunction "1_1") (pintype "passive"))
    )
    (net (code "42") (name "Net-(Q1-D)") (class "Default")
      (node (ref "Q1") (pin "3") (pinfunction "D_3") (pintype "passive"))
      (node (ref "R1") (pin "2") (pinfunction "2_2") (pintype "passive"))
    )
    (net (code "43") (name "Net-(Q2-D)") (class "Default")
      (node (ref "Q2") (pin "3") (pinfunction "D_3") (pintype "passive"))
      (node (ref "R2") (pin "2") (pinfunction "2_2") (pintype "passive"))
    )
    (net (code "44") (name "Net-(Q3-D)") (class "Default")
      (node (ref "Q3") (pin "3") (pinfunction "D_3") (pintype "passive"))
      (node (ref "R3") (pin "2") (pinfunction "2_2") (pintype "passive"))
    )
    (net (code "45") (name "Net-(U1-AREF)") (class "Default")
      (node (ref "C2") (pin "1") (pinfunction "1_1") (pintype "passive"))
      (node (ref "U1") (pin "20") (pinfunction "AREF_20") (pintype "bidirectional"))
    )
    (net (code "46") (name "Net-(U3-X1)") (class "Default")
      (node (ref "U3") (pin "1") (pinfunction "X1_1") (pintype "bidirectional"))
      (node (ref "Y1") (pin "2") (pinfunction "2_2") (pintype "passive"))
    )
    (net (code "47") (name "Net-(U3-X2)") (class "Default")
      (node (ref "U3") (pin "2") (pinfunction "X2_2") (pintype "bidirectional"))
      (node (ref "Y1") (pin "1") (pinfunction "1_1") (pintype "passive"))
    )
    (net (code "48") (name "Net-(U4-BS)") (class "Default")
      (node (ref "C12") (pin "1") (pinfunction "1_1") (pintype "passive"))
      (node (ref "U4") (pin "2") (pinfunction "BS_2") (pintype "bidirectional"))
    )
    (net (code "49") (name "Net-(U4-COMP)") (class "Default")
      (node (ref "R6") (pin "2") (pinfunction "2_2") (pintype "passive"))
      (node (ref "U4") (pin "5") (pinfunction "COMP_5") (pintype "bidirectional"))
    )
    (net (code "50") (name "Net-(U4-FB)") (class "Default")
      (node (ref "R4") (pin "1") (pinfunction "1_1") (pintype "passive"))
      (node (ref "R5") (pin "2") (pinfunction "2_2") (pintype "passive"))
      (node (ref "U4") (pin "4") (pinfunction "FB_4") (pintype "bidirectional"))
    )
    (net (code "51") (name "Net-(U4-VBIAS)") (class "Default")
      (node (ref "C13") (pin "1") (pinfunction "1_1") (pintype "passive"))
      (node (ref "U4") (pin "8") (pinfunction "VBIAS_8") (pintype "bidirectional"))
    )
    (net (code "52") (name "VIN") (class "Default")
      (node (ref "C10") (pin "+") (pinfunction "+_+") (pintype "passive"))
      (node (ref "C11") (pin "1") (pinfunction "1_1") (pintype "passive"))
      (node (ref "C15") (pin "1") (pinfunction "1_1") (pintype "passive"))
      (node (ref "J10") (pin "1") (pinfunction "1_1") (pintype "bidirectional"))
      (node (ref "J11") (pin "1") (pinfunction "1_1") (pintype "bidirectional"))
      (node (ref "J12") (pin "1") (pinfunction "1_1") (pintype "bidirectional"))
      (node (ref "J13") (pin "1") (pinfunction "1_1") (pintype "bidirectional"))
      (node (ref "J14") (pin "1") (pinfunction "1_1") (pintype "bidirectional"))
      (node (ref "J15") (pin "1") (pinfunction "1_1") (pintype "bidirectional"))
      (node (ref "J16") (pin "1") (pinfunction "1_1") (pintype "bidirectional"))
      (node (ref "J18") (pin "1") (pinfunction "1_1") (pintype "bidirectional"))
      (node (ref "J19") (pin "1") (pinfunction "1_1") (pintype "bidirectional"))
      (node (ref "J2") (pin "1") (pinfunction "1_1") (pintype "bidirectional"))
      (node (ref "J22") (pin "2") (pinfunction "S_2") (pintype "passive"))
      (node (ref "J22") (pin "4") (pinfunction "S_4") (pintype "passive"))
      (node (ref "J3") (pin "1") (pinfunction "1_1") (pintype "bidirectional"))
      (node (ref "J4") (pin "1") (pinfunction "1_1") (pintype "bidirectional"))
      (node (ref "J5") (pin "1") (pinfunction "1_1") (pintype "bidirectional"))
      (node (ref "J6") (pin "1") (pinfunction "1_1") (pintype "bidirectional"))
      (node (ref "J7") (pin "1") (pinfunction "1_1") (pintype "bidirectional"))
      (node (ref "J8") (pin "1") (pinfunction "1_1") (pintype "bidirectional"))
      (node (ref "J9") (pin "1") (pinfunction "1_1") (pintype "bidirectional"))
      (node (ref "U4") (pin "6") (pinfunction "EN_6") (pintype "bidirectional"))
      (node (ref "U4") (pin "7") (pinfunction "VIN_7") (pintype "bidirectional"))
    )
    (net (code "53") (name "unconnected-(J2-Pad3)") (class "Default")
      (node (ref "J2") (pin "3") (pinfunction "3_3") (pintype "bidirectional"))
    )
    (net (code "54") (name "unconnected-(J3-Pad3)") (class "Default")
      (node (ref "J3") (pin "3") (pinfunction "3_3") (pintype "bidirectional"))
    )
    (net (code "55") (name "unconnected-(J4-Pad3)") (class "Default")
      (node (ref "J4") (pin "3") (pinfunction "3_3") (pintype "bidirectional"))
    )
    (net (code "56") (name "unconnected-(J5-Pad3)") (class "Default")
      (node (ref "J5") (pin "3") (pinfunction "3_3") (pintype "bidirectional"))
    )
    (net (code "57") (name "unconnected-(J6-Pad3)") (class "Default")
      (node (ref "J6") (pin "3") (pinfunction "3_3") (pintype "bidirectional"))
    )
    (net (code "58") (name "unconnected-(J7-Pad3)") (class "Default")
      (node (ref "J7") (pin "3") (pinfunction "3_3") (pintype "bidirectional"))
    )
    (net (code "59") (name "unconnected-(J8-Pad3)") (class "Default")
      (node (ref "J8") (pin "3") (pinfunction "3_3") (pintype "bidirectional"))
    )
    (net (code "60") (name "unconnected-(J9-Pad3)") (class "Default")
      (node (ref "J9") (pin "3") (pinfunction "3_3") (pintype "bidirectional"))
    )
    (net (code "61") (name "unconnected-(J10-Pad3)") (class "Default")
      (node (ref "J10") (pin "3") (pinfunction "3_3") (pintype "bidirectional"))
    )
    (net (code "62") (name "unconnected-(J11-Pad3)") (class "Default")
      (node (ref "J11") (pin "3") (pinfunction "3_3") (pintype "bidirectional"))
    )
    (net (code "63") (name "unconnected-(J12-Pad3)") (class "Default")
      (node (ref "J12") (pin "3") (pinfunction "3_3") (pintype "bidirectional"))
    )
    (net (code "64") (name "unconnected-(J13-Pad3)") (class "Default")
      (node (ref "J13") (pin "3") (pinfunction "3_3") (pintype "bidirectional"))
    )
    (net (code "65") (name "unconnected-(J14-Pad3)") (class "Default")
      (node (ref "J14") (pin "3") (pinfunction "3_3") (pintype "bidirectional"))
    )
    (net (code "66") (name "unconnected-(J15-Pad3)") (class "Default")
      (node (ref "J15") (pin "3") (pinfunction "3_3") (pintype "bidirectional"))
    )
    (net (code "67") (name "unconnected-(J16-Pad3)") (class "Default")
      (node (ref "J16") (pin "3") (pinfunction "3_3") (pintype "bidirectional"))
    )
    (net (code "68") (name "unconnected-(J17-GPIO4,GPCLK0-PadP1_7)") (class "Default")
      (node (ref "J17") (pin "P1_7") (pinfunction "GPIO4,GPCLK0_P1_7") (pintype "bidirectional"))
    )
    (net (code "69") (name "unconnected-(J17-GPIO17-PadP1_11)") (class "Default")
      (node (ref "J17") (pin "P1_11") (pinfunction "GPIO17_P1_11") (pintype "bidirectional"))
    )
    (net (code "70") (name "unconnected-(J17-GPIO18-PadP1_12)") (class "Default")
      (node (ref "J17") (pin "P1_12") (pinfunction "GPIO18_P1_12") (pintype "bidirectional"))
    )
    (net (code "71") (name "unconnected-(J17-GPIO22-PadP1_15)") (class "Default")
      (node (ref "J17") (pin "P1_15") (pinfunction "GPIO22_P1_15") (pintype "bidirectional"))
    )
    (net (code "72") (name "unconnected-(J17-GPIO27-PadP1_13)") (class "Default")
      (node (ref "J17") (pin "P1_13") (pinfunction "GPIO27_P1_13") (pintype "bidirectional"))
    )
    (net (code "73") (name "unconnected-(J18-Pad3)") (class "Default")
      (node (ref "J18") (pin "3") (pinfunction "3_3") (pintype "bidirectional"))
    )
    (net (code "74") (name "unconnected-(J19-Pad3)") (class "Default")
      (node (ref "J19") (pin "3") (pinfunction "3_3") (pintype "bidirectional"))
    )
    (net (code "75") (name "unconnected-(U1-ADC6-Pad19)") (class "Default")
      (node (ref "U1") (pin "19") (pinfunction "ADC6_19") (pintype "bidirectional"))
    )
    (net (code "76") (name "unconnected-(U1-ADC7-Pad22)") (class "Default")
      (node (ref "U1") (pin "22") (pinfunction "ADC7_22") (pintype "bidirectional"))
    )
    (net (code "77") (name "unconnected-(U3-SQW-Pad7)") (class "Default")
      (node (ref "U3") (pin "7") (pinfunction "SQW_7") (pintype "bidirectional"))
    )
  )
)
